# Current_Mirror_1.net
KiCad netlist of a schematic drawn in Altium Designer
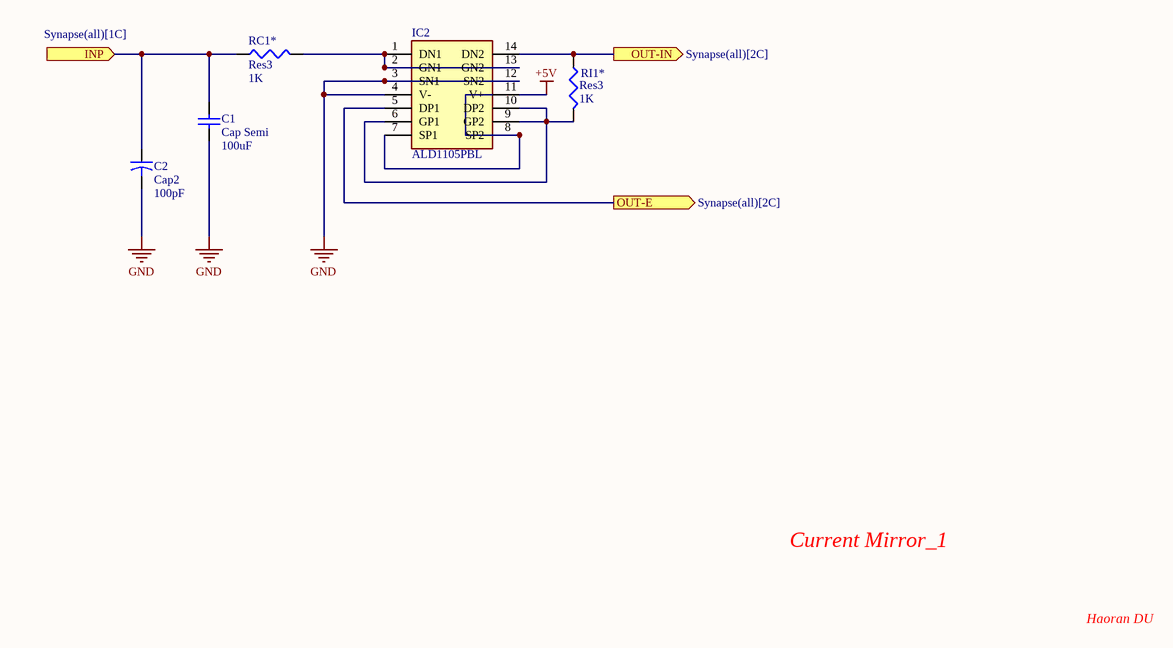
[diagram p0: Current Mirror_1.SchDoc]

(export (version "E")
  (design (tool "Eeschema 10.0.6"))
  (components
    (comp (ref "C1")
      (value "Cap Semi")
      (footprint "C1206")
      (description "Capacitor (Semiconductor SIM Model)")
      (fields (field (name "ALTIUM_VALUE") "100uF") (field (name "PUBLISHER") "Altium Limited"))
      (libsource (lib "Miscellaneous Devices") (part "Cap Semi"))
    )
    (comp (ref "C2")
      (value "Cap2")
      (footprint "CAPR5-4X5")
      (description "Capacitor")
      (fields (field (name "ALTIUM_VALUE") "100pF") (field (name "PUBLISHER") "Altium Limited"))
      (libsource (lib "Miscellaneous Devices") (part "Cap2"))
    )
    (comp (ref "IC2")
      (value "ALD1105PBL")
      (footprint "SamacSys:DIP762W51P254L1828H508Q14N")
      (description "Integrated Circuit")
      (fields (field (name "MOUSER PART NUMBER") "585-ALD1105PBL"))
      (libsource (lib "*") (part "ALD1105PBL"))
    )
    (comp (ref "RC1*")
      (value "Res3")
      (footprint "J1-0603")
      (description "Resistor")
      (fields (field (name "ALTIUM_VALUE") "1K") (field (name "PUBLISHER") "Altium Limited"))
      (libsource (lib "Miscellaneous Devices") (part "Res3"))
    )
    (comp (ref "RI1*")
      (value "Res3")
      (footprint "J1-0603")
      (description "Resistor")
      (fields (field (name "ALTIUM_VALUE") "1K") (field (name "PUBLISHER") "Altium Limited"))
      (libsource (lib "Miscellaneous Devices") (part "Res3"))
    )
  )
  (nets
    (net (code "1") (name "+5V") (class "Default")
      (node (ref "IC2") (pin "11") (pinfunction "V+_11") (pintype "passive"))
    )
    (net (code "2") (name "/INP") (class "Default")
      (node (ref "C1") (pin "2") (pinfunction "2_2") (pintype "passive"))
      (node (ref "C2") (pin "1") (pinfunction "1_1") (pintype "passive"))
      (node (ref "RC1*") (pin "1") (pinfunction "1_1") (pintype "passive"))
    )
    (net (code "3") (name "/OUT-E") (class "Default")
      (node (ref "IC2") (pin "5") (pinfunction "DP1_5") (pintype "passive"))
    )
    (net (code "4") (name "/OUT-IN") (class "Default")
      (node (ref "IC2") (pin "14") (pinfunction "DN2_14") (pintype "passive"))
      (node (ref "RI1*") (pin "1") (pinfunction "1_1") (pintype "passive"))
    )
    (net (code "5") (name "GND") (class "Default")
      (node (ref "C1") (pin "1") (pinfunction "1_1") (pintype "passive"))
      (node (ref "C2") (pin "2") (pinfunction "2_2") (pintype "passive"))
      (node (ref "IC2") (pin "12") (pinfunction "SN2_12") (pintype "passive"))
      (node (ref "IC2") (pin "3") (pinfunction "SN1_3") (pintype "passive"))
      (node (ref "IC2") (pin "4") (pinfunction "V-_4") (pintype "passive"))
    )
    (net (code "6") (name "Net-(IC2-DN1)") (class "Default")
      (node (ref "IC2") (pin "1") (pinfunction "DN1_1") (pintype "passive"))
      (node (ref "IC2") (pin "13") (pinfunction "GN2_13") (pintype "passive"))
      (node (ref "IC2") (pin "2") (pinfunction "GN1_2") (pintype "passive"))
      (node (ref "RC1*") (pin "2") (pinfunction "2_2") (pintype "passive"))
    )
    (net (code "7") (name "Net-(IC2-DP2)") (class "Default")
      (node (ref "IC2") (pin "10") (pinfunction "DP2_10") (pintype "passive"))
      (node (ref "IC2") (pin "6") (pinfunction "GP1_6") (pintype "passive"))
      (node (ref "IC2") (pin "9") (pinfunction "GP2_9") (pintype "passive"))
      (node (ref "RI1*") (pin "2") (pinfunction "2_2") (pintype "passive"))
    )
    (net (code "8") (name "Net-(IC2-SP1)") (class "Default")
      (node (ref "IC2") (pin "7") (pinfunction "SP1_7") (pintype "passive"))
      (node (ref "IC2") (pin "8") (pinfunction "SP2_8") (pintype "passive"))
    )
  )
)
